# Sheet1.net
KiCad netlist of a schematic drawn in Altium Designer
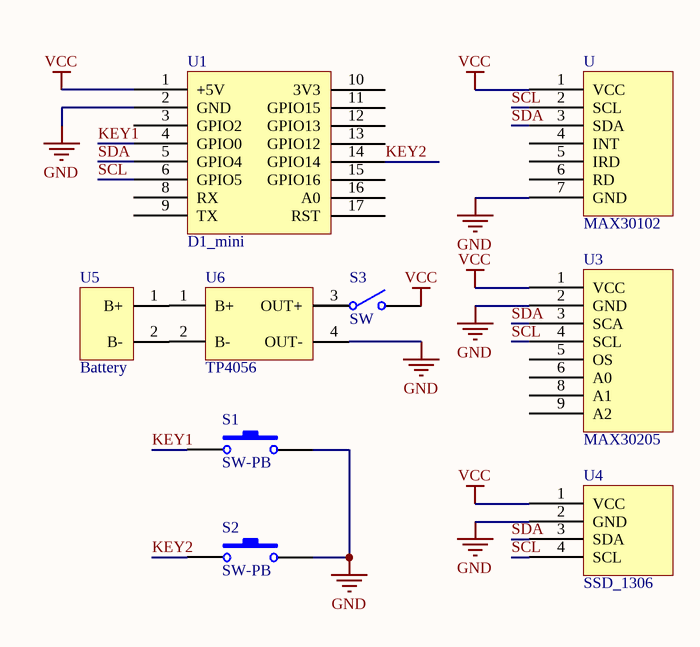
[diagram p0: Sheet1.SchDoc]

(export (version "E")
  (design (tool "Eeschema 10.0.6"))
  (components
    (comp (ref "S1")
      (value "SW-PB")
      (footprint "SPST-2")
      (description "Switch")
      (fields (field (name "PUBLISHER") "Altium Limited"))
      (libsource (lib "Miscellaneous Devices") (part "SW-PB"))
    )
    (comp (ref "S2")
      (value "SW-PB")
      (footprint "SPST-2")
      (description "Switch")
      (fields (field (name "PUBLISHER") "Altium Limited"))
      (libsource (lib "Miscellaneous Devices") (part "SW-PB"))
    )
    (comp (ref "S3")
      (value "SW")
      (footprint "SPST-2")
      (description "Single-Pole, Single-Throw Switch")
      (fields (field (name "PUBLISHER") "Altium Limited"))
      (libsource (lib "Miscellaneous Devices") (part "SW-SPST"))
    )
    (comp (ref "U") (value "MAX30102") (libsource (lib "Schlib1") (part "MAX30102")))
    (comp (ref "U1") (value "D1_mini") (libsource (lib "Schlib1") (part "D1_mini")))
    (comp (ref "U3") (value "MAX30205") (libsource (lib "Schlib1") (part "MAX30205")))
    (comp (ref "U4") (value "SSD_1306") (libsource (lib "Schlib1") (part "SSD_1306")))
    (comp (ref "U5") (value "Battery") (libsource (lib "Schlib1") (part "Battery")))
    (comp (ref "U6") (value "TP4056") (libsource (lib "Schlib1") (part "TP4056")))
  )
  (nets
    (net (code "1") (name "/KEY1") (class "Default")
      (node (ref "S1") (pin "1") (pinfunction "1_1") (pintype "passive"))
      (node (ref "U1") (pin "4") (pinfunction "GPIO0_4") (pintype "passive"))
    )
    (net (code "2") (name "/KEY2") (class "Default")
      (node (ref "S2") (pin "1") (pinfunction "1_1") (pintype "passive"))
      (node (ref "U1") (pin "14") (pinfunction "GPIO14_14") (pintype "passive"))
    )
    (net (code "3") (name "/SCL") (class "Default")
      (node (ref "U") (pin "2") (pinfunction "SCL_2") (pintype "passive"))
      (node (ref "U1") (pin "6") (pinfunction "GPIO5_6") (pintype "passive"))
      (node (ref "U3") (pin "4") (pinfunction "SCL_4") (pintype "passive"))
      (node (ref "U4") (pin "4") (pinfunction "SCL_4") (pintype "passive"))
    )
    (net (code "4") (name "/SDA") (class "Default")
      (node (ref "U") (pin "3") (pinfunction "SDA_3") (pintype "passive"))
      (node (ref "U1") (pin "5") (pinfunction "GPIO4_5") (pintype "passive"))
      (node (ref "U3") (pin "3") (pinfunction "SCA_3") (pintype "passive"))
      (node (ref "U4") (pin "3") (pinfunction "SDA_3") (pintype "passive"))
    )
    (net (code "5") (name "GND") (class "Default")
      (node (ref "S1") (pin "2") (pinfunction "2_2") (pintype "passive"))
      (node (ref "S2") (pin "2") (pinfunction "2_2") (pintype "passive"))
      (node (ref "U") (pin "7") (pinfunction "GND_7") (pintype "passive"))
      (node (ref "U1") (pin "2") (pinfunction "GND_2") (pintype "passive"))
      (node (ref "U3") (pin "2") (pinfunction "GND_2") (pintype "passive"))
      (node (ref "U4") (pin "2") (pinfunction "GND_2") (pintype "passive"))
      (node (ref "U6") (pin "4") (pinfunction "OUT-_4") (pintype "power_in"))
    )
    (net (code "6") (name "Net-(U5-B+)") (class "Default")
      (node (ref "U5") (pin "1") (pinfunction "B+_1") (pintype "passive"))
      (node (ref "U6") (pin "1") (pinfunction "B+_1") (pintype "passive"))
    )
    (net (code "7") (name "Net-(U5-B-)") (class "Default")
      (node (ref "U5") (pin "2") (pinfunction "B-_2") (pintype "passive"))
      (node (ref "U6") (pin "2") (pinfunction "B-_2") (pintype "passive"))
    )
    (net (code "8") (name "VCC") (class "Default")
      (node (ref "S3") (pin "2") (pinfunction "NO_2") (pintype "passive"))
      (node (ref "U") (pin "1") (pinfunction "VCC_1") (pintype "passive"))
      (node (ref "U1") (pin "1") (pinfunction "+5V_1") (pintype "passive"))
      (node (ref "U3") (pin "1") (pinfunction "VCC_1") (pintype "passive"))
      (node (ref "U4") (pin "1") (pinfunction "VCC_1") (pintype "passive"))
    )
    (net (code "9") (name "unconnected-(S3-COMMON-Pad1)") (class "Default")
      (node (ref "S3") (pin "1") (pinfunction "COMMON_1") (pintype "passive"))
    )
    (net (code "10") (name "unconnected-(U-INT-Pad4)") (class "Default")
      (node (ref "U") (pin "4") (pinfunction "INT_4") (pintype "passive"))
    )
    (net (code "11") (name "unconnected-(U-IRD-Pad5)") (class "Default")
      (node (ref "U") (pin "5") (pinfunction "IRD_5") (pintype "passive"))
    )
    (net (code "12") (name "unconnected-(U-RD-Pad6)") (class "Default")
      (node (ref "U") (pin "6") (pinfunction "RD_6") (pintype "passive"))
    )
    (net (code "13") (name "unconnected-(U1-3V3-Pad10)") (class "Default")
      (node (ref "U1") (pin "10") (pinfunction "3V3_10") (pintype "passive"))
    )
    (net (code "14") (name "unconnected-(U1-A0-Pad16)") (class "Default")
      (node (ref "U1") (pin "16") (pinfunction "A0_16") (pintype "passive"))
    )
    (net (code "15") (name "unconnected-(U1-GPIO2-Pad3)") (class "Default")
      (node (ref "U1") (pin "3") (pinfunction "GPIO2_3") (pintype "passive"))
    )
    (net (code "16") (name "unconnected-(U1-GPIO12-Pad13)") (class "Default")
      (node (ref "U1") (pin "13") (pinfunction "GPIO12_13") (pintype "passive"))
    )
    (net (code "17") (name "unconnected-(U1-GPIO13-Pad12)") (class "Default")
      (node (ref "U1") (pin "12") (pinfunction "GPIO13_12") (pintype "passive"))
    )
    (net (code "18") (name "unconnected-(U1-GPIO15-Pad11)") (class "Default")
      (node (ref "U1") (pin "11") (pinfunction "GPIO15_11") (pintype "passive"))
    )
    (net (code "19") (name "unconnected-(U1-GPIO16-Pad15)") (class "Default")
      (node (ref "U1") (pin "15") (pinfunction "GPIO16_15") (pintype "passive"))
    )
    (net (code "20") (name "unconnected-(U1-RST-Pad17)") (class "Default")
      (node (ref "U1") (pin "17") (pinfunction "RST_17") (pintype "passive"))
    )
    (net (code "21") (name "unconnected-(U1-RX-Pad8)") (class "Default")
      (node (ref "U1") (pin "8") (pinfunction "RX_8") (pintype "passive"))
    )
    (net (code "22") (name "unconnected-(U1-TX-Pad9)") (class "Default")
      (node (ref "U1") (pin "9") (pinfunction "TX_9") (pintype "passive"))
    )
    (net (code "23") (name "unconnected-(U3-A0-Pad6)") (class "Default")
      (node (ref "U3") (pin "6") (pinfunction "A0_6") (pintype "passive"))
    )
    (net (code "24") (name "unconnected-(U3-A1-Pad8)") (class "Default")
      (node (ref "U3") (pin "8") (pinfunction "A1_8") (pintype "passive"))
    )
    (net (code "25") (name "unconnected-(U3-A2-Pad9)") (class "Default")
      (node (ref "U3") (pin "9") (pinfunction "A2_9") (pintype "passive"))
    )
    (net (code "26") (name "unconnected-(U3-OS-Pad5)") (class "Default")
      (node (ref "U3") (pin "5") (pinfunction "OS_5") (pintype "passive"))
    )
    (net (code "27") (name "unconnected-(U6-OUT+-Pad3)") (class "Default")
      (node (ref "U6") (pin "3") (pinfunction "OUT+_3") (pintype "power_in"))
    )
  )
)
